# 6_channel_esp32_energy_meter_add-on_1_3_.net
KiCad netlist of a schematic drawn in EAGLE
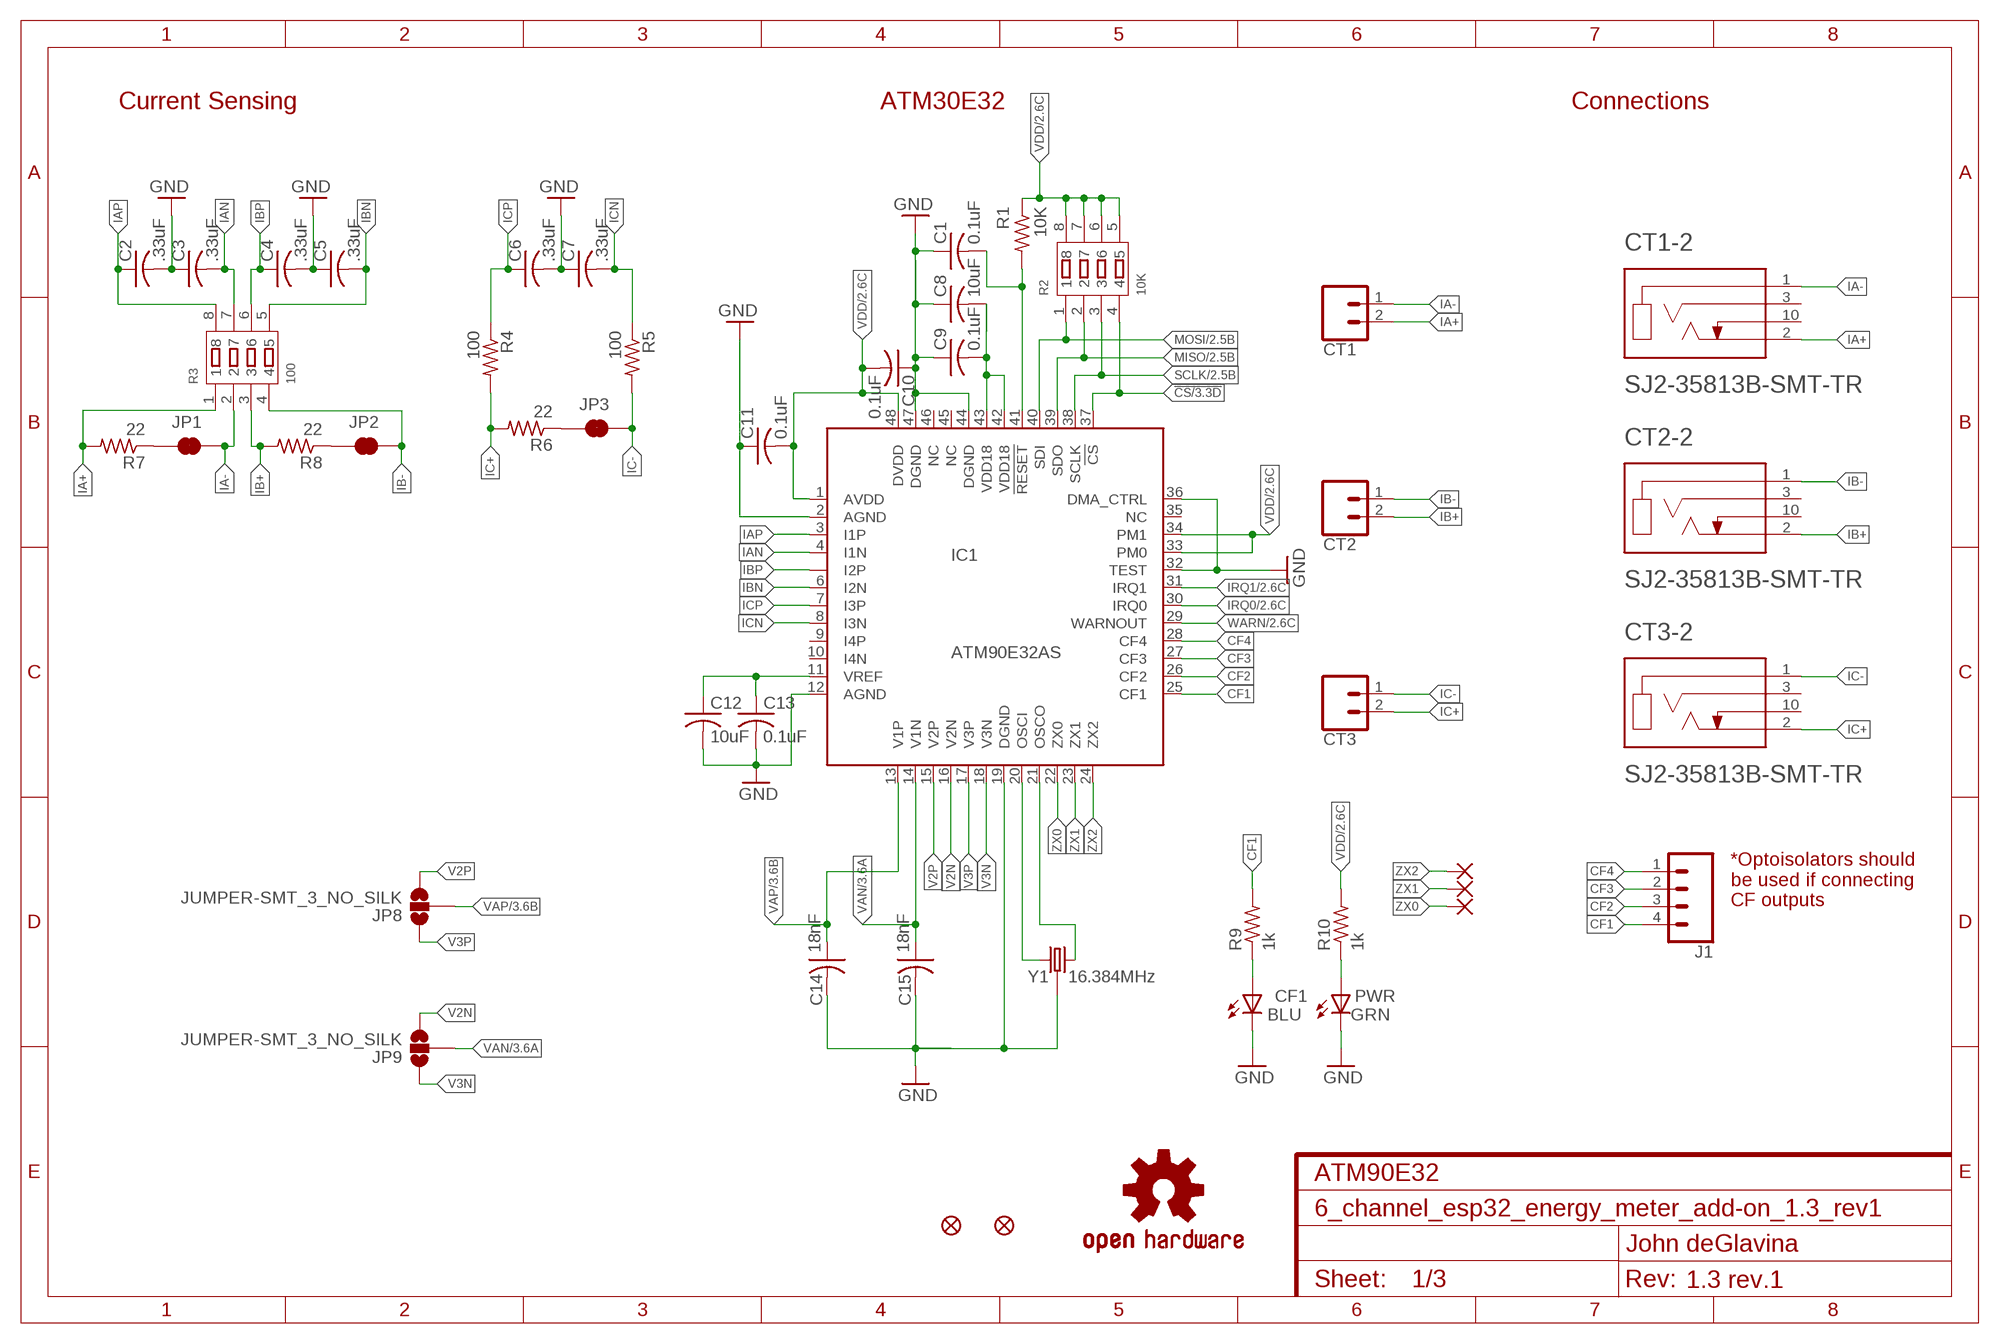
[diagram p0: schematic, sheet 1]
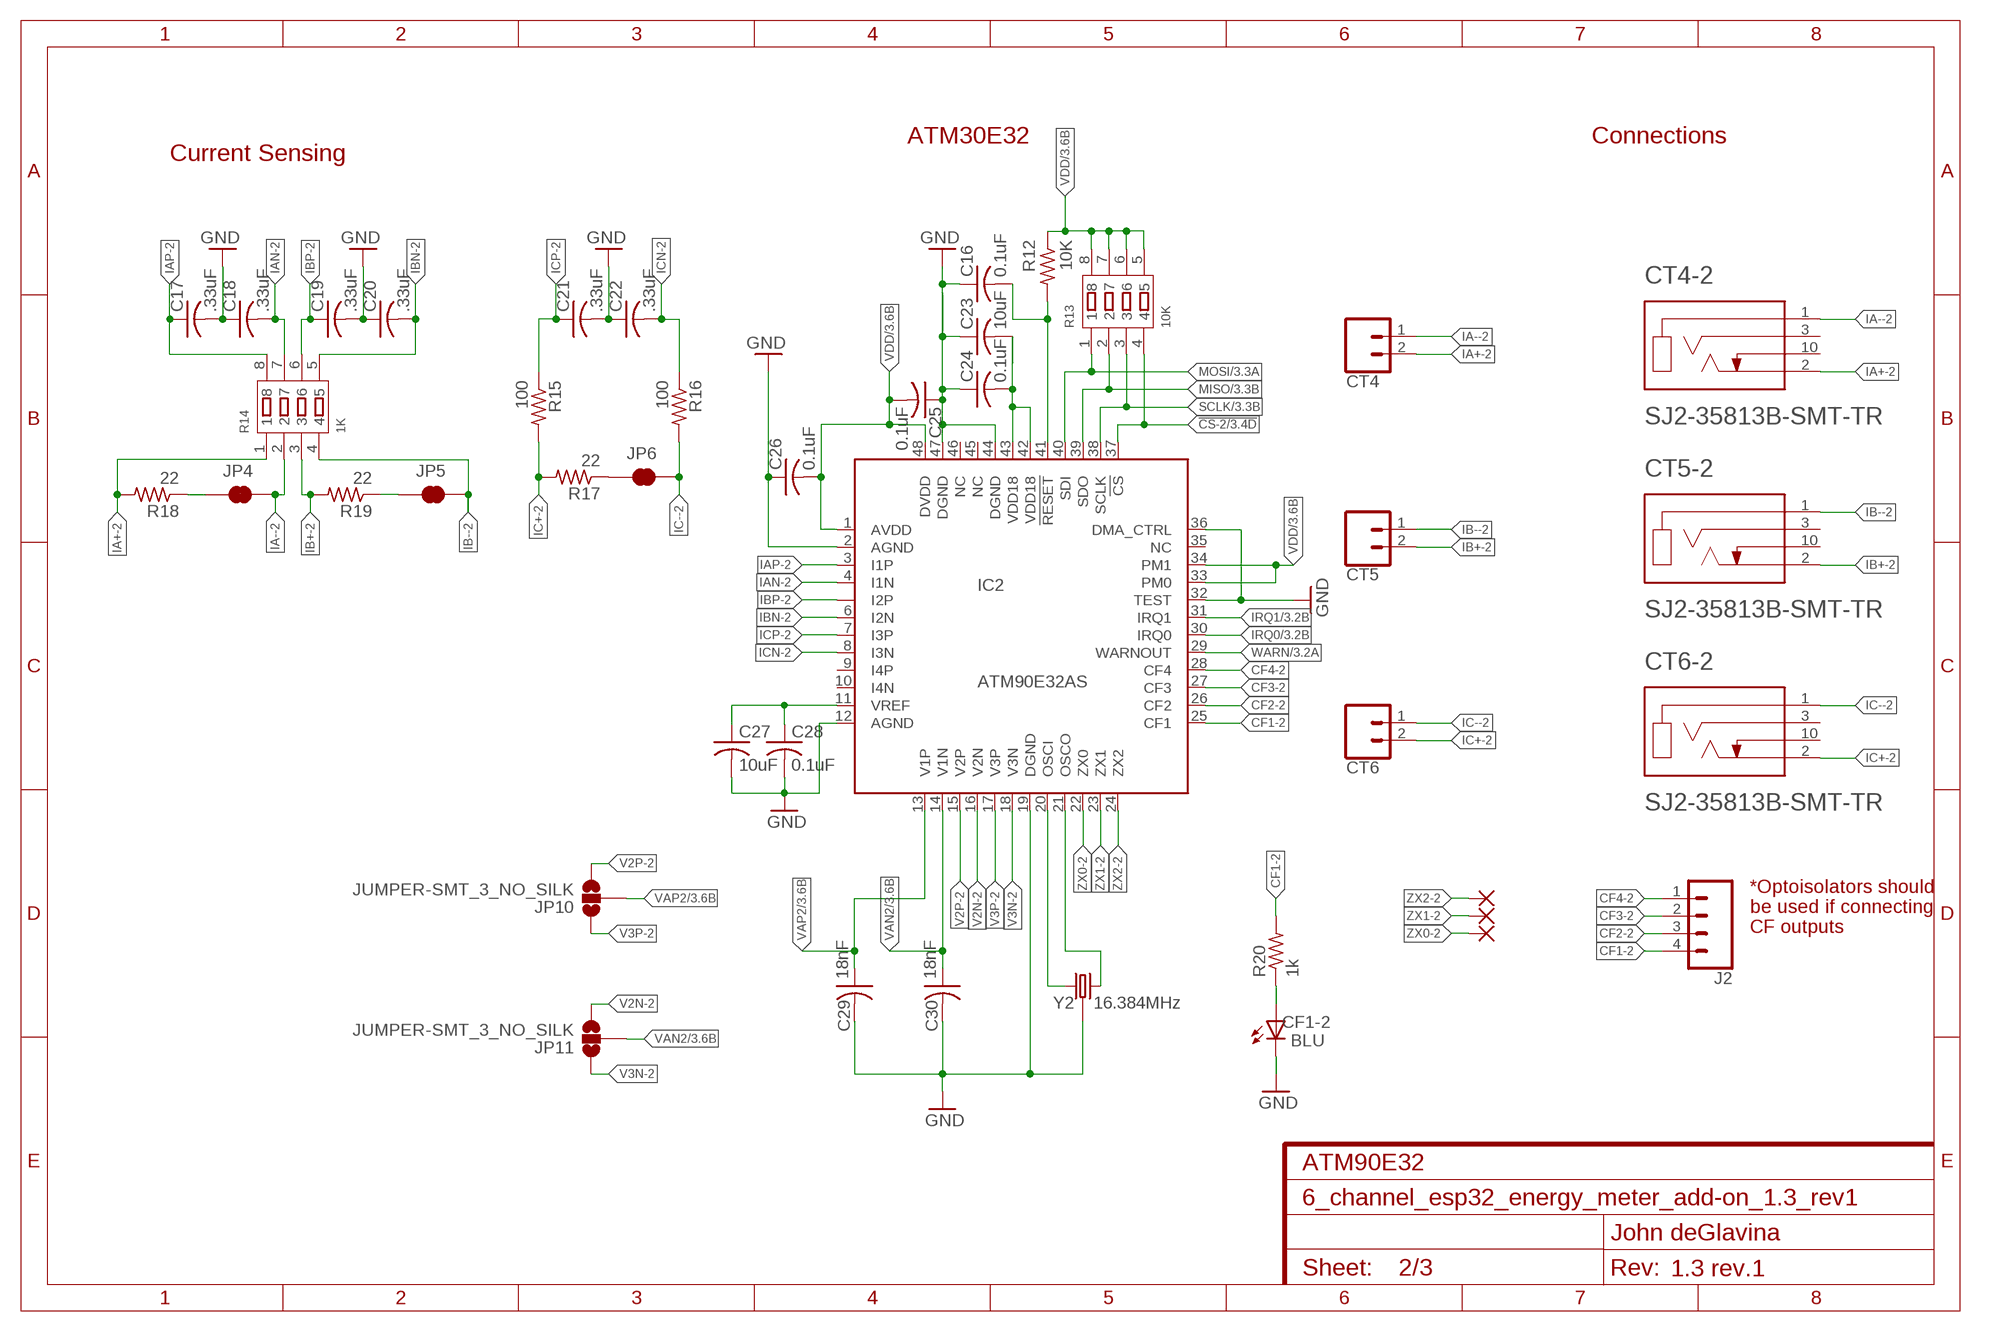
[diagram p1: schematic, sheet 2]
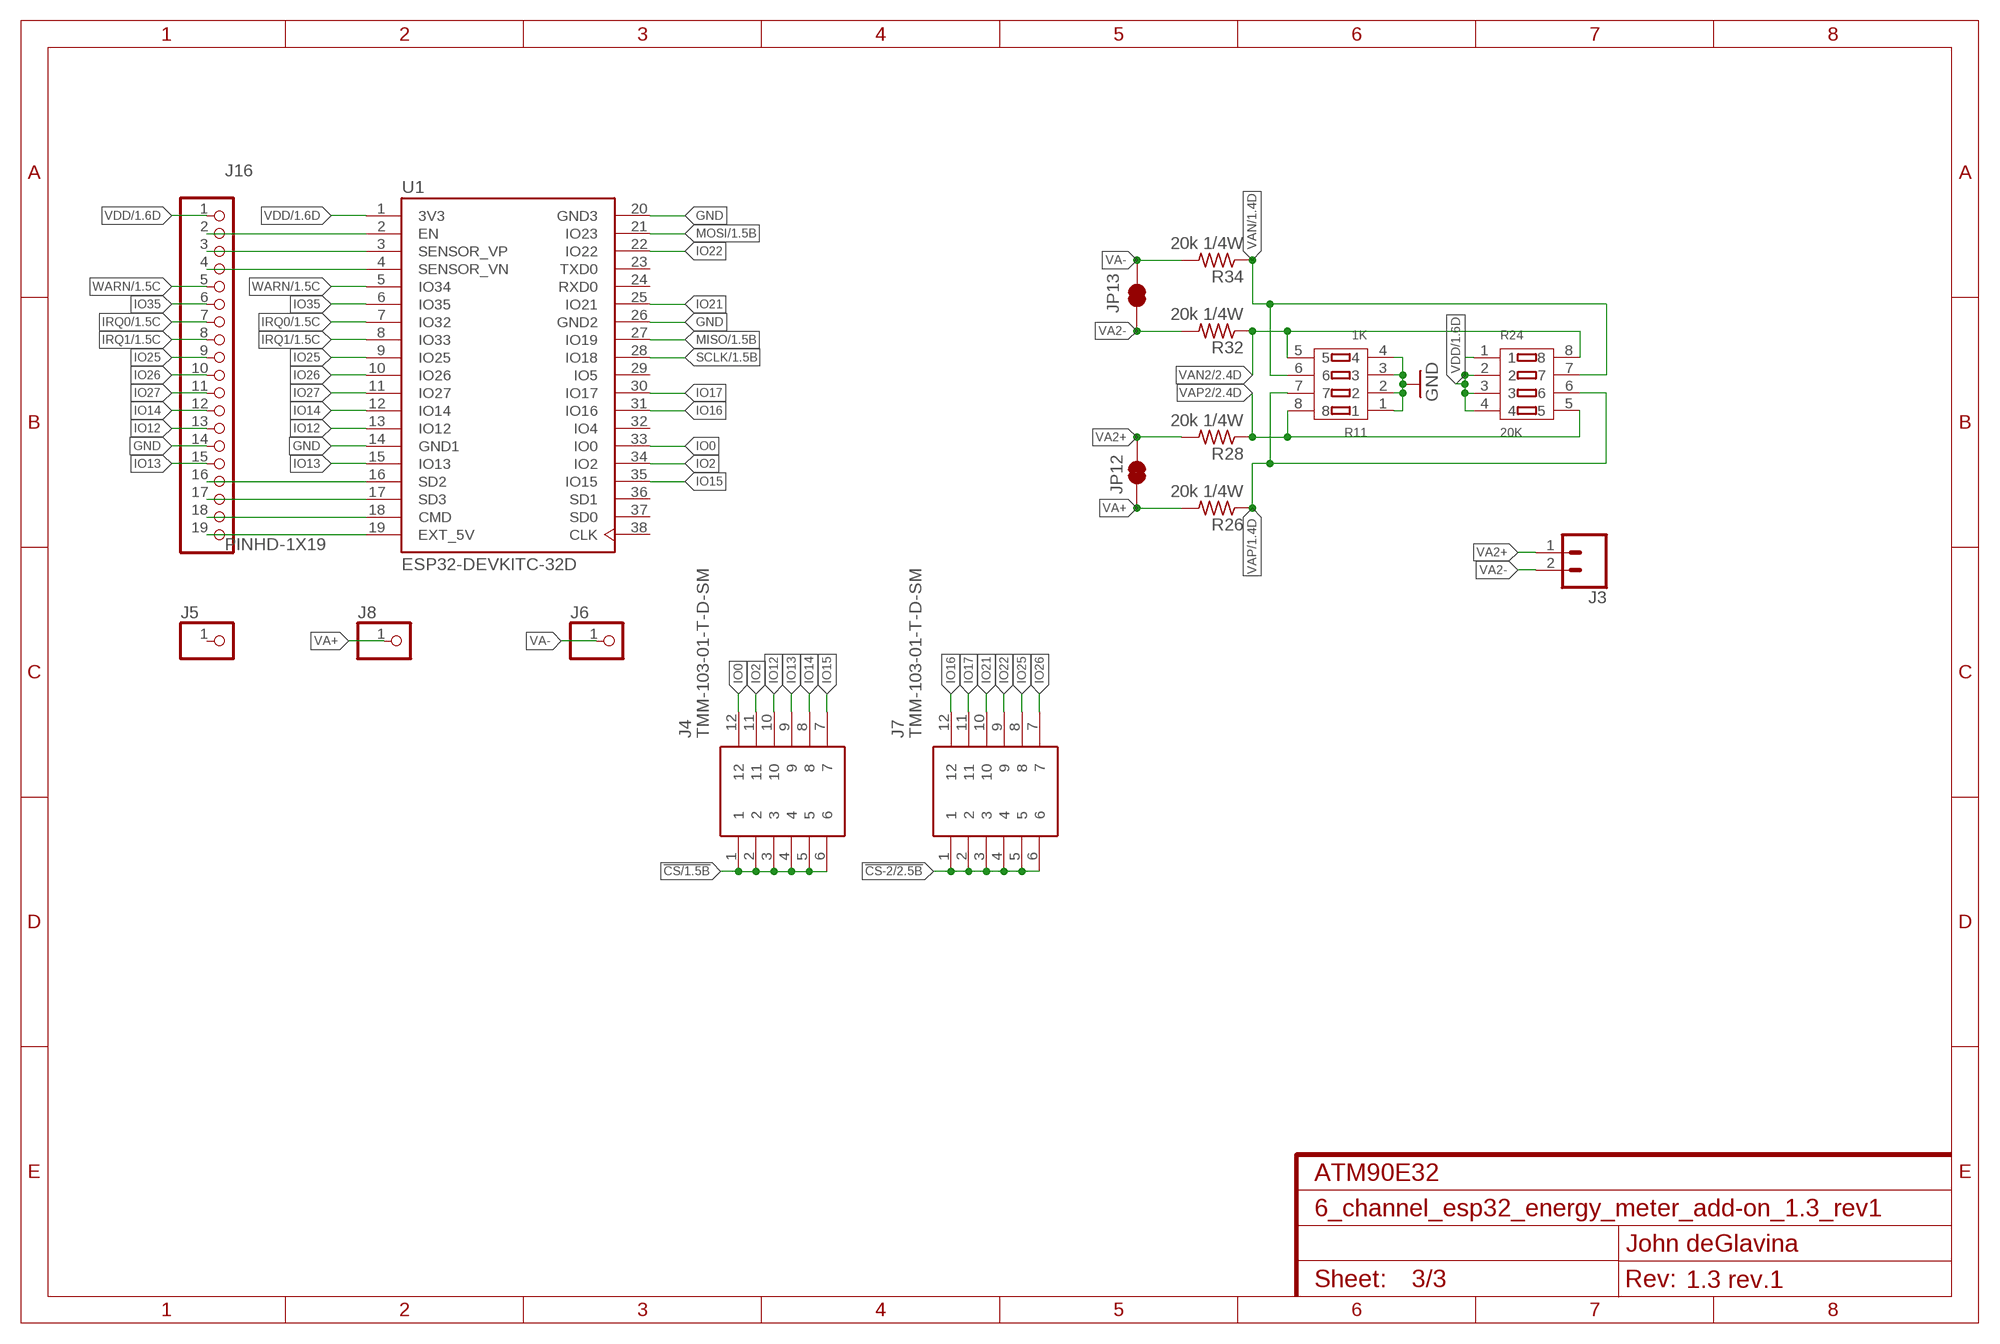
[diagram p2: schematic, sheet 3]

(export (version "E")
  (design (tool "Eeschema 10.0.6"))
  (components
    (comp (ref "C1")
      (value "0.1uF")
      (footprint "eagle-import:C0603")
      (libsource (lib "eagle-import") (part "C-USC0603"))
    )
    (comp (ref "C2")
      (value ".33uF")
      (footprint "eagle-import:C0603")
      (libsource (lib "eagle-import") (part "C-USC0603"))
    )
    (comp (ref "C3")
      (value ".33uF")
      (footprint "eagle-import:C0603")
      (libsource (lib "eagle-import") (part "C-USC0603"))
    )
    (comp (ref "C4")
      (value ".33uF")
      (footprint "eagle-import:C0603")
      (libsource (lib "eagle-import") (part "C-USC0603"))
    )
    (comp (ref "C5")
      (value ".33uF")
      (footprint "eagle-import:C0603")
      (libsource (lib "eagle-import") (part "C-USC0603"))
    )
    (comp (ref "C6")
      (value ".33uF")
      (footprint "eagle-import:C0603")
      (libsource (lib "eagle-import") (part "C-USC0603"))
    )
    (comp (ref "C7")
      (value ".33uF")
      (footprint "eagle-import:C0603")
      (libsource (lib "eagle-import") (part "C-USC0603"))
    )
    (comp (ref "C8")
      (value "10uF")
      (footprint "eagle-import:C0603")
      (libsource (lib "eagle-import") (part "C-USC0603"))
    )
    (comp (ref "C9")
      (value "0.1uF")
      (footprint "eagle-import:C0603")
      (libsource (lib "eagle-import") (part "C-USC0603"))
    )
    (comp (ref "C10")
      (value "0.1uF")
      (footprint "eagle-import:C0603")
      (libsource (lib "eagle-import") (part "C-USC0603"))
    )
    (comp (ref "C11")
      (value "0.1uF")
      (footprint "eagle-import:C0603")
      (libsource (lib "eagle-import") (part "C-USC0603"))
    )
    (comp (ref "C12")
      (value "10uF")
      (footprint "eagle-import:C0603")
      (libsource (lib "eagle-import") (part "C-USC0603"))
    )
    (comp (ref "C13")
      (value "0.1uF")
      (footprint "eagle-import:C0603")
      (libsource (lib "eagle-import") (part "C-USC0603"))
    )
    (comp (ref "C14")
      (value "18nF")
      (footprint "eagle-import:C0603")
      (libsource (lib "eagle-import") (part "C-USC0603"))
    )
    (comp (ref "C15")
      (value "18nF")
      (footprint "eagle-import:C0603")
      (libsource (lib "eagle-import") (part "C-USC0603"))
    )
    (comp (ref "CF1")
      (value "BLU")
      (footprint "eagle-import:CHIPLED_0603")
      (libsource (lib "eagle-import") (part "LEDCHIPLED_0603"))
    )
    (comp (ref "CT1")
      (value "CONN_023.5MM")
      (footprint "eagle-import:SCREWTERMINAL-3.5MM-2")
      (libsource (lib "eagle-import") (part "SparkFun-Connectors_8231346_CONN_023.5MM"))
    )
    (comp (ref "CT1-2")
      (value "SJ2-35813B-SMT-TR")
      (footprint "eagle-import:CUI_SJ2-35813B-SMT-TR")
      (fields (field (name "MANUFACTURER") "CUI"))
      (libsource (lib "eagle-import") (part "SJ2-35813B-SMT-TR"))
    )
    (comp (ref "CT2")
      (value "CONN_023.5MM")
      (footprint "eagle-import:SCREWTERMINAL-3.5MM-2")
      (libsource (lib "eagle-import") (part "SparkFun-Connectors_8231346_CONN_023.5MM"))
    )
    (comp (ref "CT2-2")
      (value "SJ2-35813B-SMT-TR")
      (footprint "eagle-import:CUI_SJ2-35813B-SMT-TR")
      (fields (field (name "MANUFACTURER") "CUI"))
      (libsource (lib "eagle-import") (part "SJ2-35813B-SMT-TR"))
    )
    (comp (ref "CT3")
      (value "CONN_023.5MM")
      (footprint "eagle-import:SCREWTERMINAL-3.5MM-2")
      (libsource (lib "eagle-import") (part "SparkFun-Connectors_8231346_CONN_023.5MM"))
    )
    (comp (ref "CT3-2")
      (value "SJ2-35813B-SMT-TR")
      (footprint "eagle-import:CUI_SJ2-35813B-SMT-TR")
      (fields (field (name "MANUFACTURER") "CUI"))
      (libsource (lib "eagle-import") (part "SJ2-35813B-SMT-TR"))
    )
    (comp (ref "FD1")
      (value "FIDUCIALUFIDUCIAL")
      (footprint "eagle-import:FIDUCIAL-MICRO")
      (libsource (lib "eagle-import") (part "FIDUCIALUFIDUCIAL"))
    )
    (comp (ref "FD2")
      (value "FIDUCIALUFIDUCIAL")
      (footprint "eagle-import:FIDUCIAL-MICRO")
      (libsource (lib "eagle-import") (part "FIDUCIALUFIDUCIAL"))
    )
    (comp (ref "IC1")
      (value "ATM90E32AS")
      (footprint "eagle-import:QFP50P900X900X120-48")
      (fields (field (name "SPICEPREFIX") "X"))
      (libsource (lib "eagle-import") (part "ATM90E36"))
    )
    (comp (ref "J1")
      (value "CONN_04")
      (footprint "eagle-import:1X04")
      (libsource (lib "eagle-import") (part "CONN_04"))
    )
    (comp (ref "JP1")
      (value "JUMPER-SMT_2_NC_TRACE_SILK")
      (footprint "eagle-import:SMT-JUMPER_2_NC_TRACE_SILK")
      (libsource (lib "eagle-import") (part "JUMPER-SMT_2_NC_TRACE_SILK"))
    )
    (comp (ref "JP2")
      (value "JUMPER-SMT_2_NC_TRACE_SILK")
      (footprint "eagle-import:SMT-JUMPER_2_NC_TRACE_SILK")
      (libsource (lib "eagle-import") (part "JUMPER-SMT_2_NC_TRACE_SILK"))
    )
    (comp (ref "JP3")
      (value "JUMPER-SMT_2_NC_TRACE_SILK")
      (footprint "eagle-import:SMT-JUMPER_2_NC_TRACE_SILK")
      (libsource (lib "eagle-import") (part "JUMPER-SMT_2_NC_TRACE_SILK"))
    )
    (comp (ref "JP8")
      (value "JUMPER-SMT_3_NO_SILK")
      (footprint "eagle-import:SMT-JUMPER_3_NO_SILK")
      (libsource (lib "eagle-import") (part "JUMPER-SMT_3_NO_SILK"))
    )
    (comp (ref "JP9")
      (value "JUMPER-SMT_3_NO_SILK")
      (footprint "eagle-import:SMT-JUMPER_3_NO_SILK")
      (libsource (lib "eagle-import") (part "JUMPER-SMT_3_NO_SILK"))
    )
    (comp (ref "LOGO1")
      (value "OSHW-LOGOS")
      (footprint "eagle-import:OSHW-LOGO-S")
      (libsource (lib "eagle-import") (part "OSHW-LOGOS"))
    )
    (comp (ref "PWR")
      (value "GRN")
      (footprint "eagle-import:CHIPLED_0603")
      (libsource (lib "eagle-import") (part "LEDCHIPLED_0603"))
    )
    (comp (ref "R1")
      (value "10K")
      (footprint "eagle-import:R0603")
      (libsource (lib "eagle-import") (part "R-US_R0603"))
    )
    (comp (ref "R2")
      (value "10K")
      (footprint "eagle-import:RA1206-8")
      (fields (field (name "MPN") "Chip-Array-Series-1%"))
      (libsource (lib "eagle-import") (part "SMD-RES-ARRAY-1K-4R(RA1206-8)"))
    )
    (comp (ref "R3")
      (value "100")
      (footprint "eagle-import:RA1206-8")
      (fields (field (name "MPN") "Chip-Array-Series-1%"))
      (libsource (lib "eagle-import") (part "SMD-RES-ARRAY-1K-4R(RA1206-8)"))
    )
    (comp (ref "R4")
      (value "100")
      (footprint "eagle-import:R0603")
      (libsource (lib "eagle-import") (part "R-US_R0603"))
    )
    (comp (ref "R5")
      (value "100")
      (footprint "eagle-import:R0603")
      (libsource (lib "eagle-import") (part "R-US_R0603"))
    )
    (comp (ref "R6")
      (value "22")
      (footprint "eagle-import:R0603")
      (libsource (lib "eagle-import") (part "R-US_R0603"))
    )
    (comp (ref "R7")
      (value "22")
      (footprint "eagle-import:R0603")
      (libsource (lib "eagle-import") (part "R-US_R0603"))
    )
    (comp (ref "R8")
      (value "22")
      (footprint "eagle-import:R0603")
      (libsource (lib "eagle-import") (part "R-US_R0603"))
    )
    (comp (ref "R9")
      (value "1k")
      (footprint "eagle-import:R0603")
      (libsource (lib "eagle-import") (part "R-US_R0603"))
    )
    (comp (ref "R10")
      (value "1k")
      (footprint "eagle-import:R0603")
      (libsource (lib "eagle-import") (part "R-US_R0603"))
    )
    (comp (ref "Y1")
      (value "16.384MHz")
      (footprint "eagle-import:CRYSTAL-SMD-3.2X2.5MM")
      (libsource (lib "eagle-import") (part "CRYSTAL-GROUNDEDSMD-3.2X2.5"))
    )
    (comp (ref "ZX0")
      (value "WIREPADSMD1,27-254")
      (footprint "eagle-import:SMD1,27-2,54")
      (libsource (lib "eagle-import") (part "WIREPADSMD1,27-254"))
    )
    (comp (ref "ZX1")
      (value "WIREPADSMD1,27-254")
      (footprint "eagle-import:SMD1,27-2,54")
      (libsource (lib "eagle-import") (part "WIREPADSMD1,27-254"))
    )
    (comp (ref "ZX2")
      (value "WIREPADSMD1,27-254")
      (footprint "eagle-import:SMD1,27-2,54")
      (libsource (lib "eagle-import") (part "WIREPADSMD1,27-254"))
    )
    (comp (ref "J3")
      (value "CONN_02")
      (footprint "eagle-import:1X02")
      (libsource (lib "eagle-import") (part "CONN_02"))
    )
    (comp (ref "J4")
      (value "TMM-103-01-T-D-SM")
      (footprint "eagle-import:SOP200P706X597-12N")
      (libsource (lib "eagle-import") (part "TMM-103-01-T-D-SM"))
    )
    (comp (ref "J5")
      (value "PINHD1X1-SM1X01_SM")
      (footprint "eagle-import:1X01-SM")
      (libsource (lib "eagle-import") (part "PINHD1X1-SM1X01_SM"))
    )
    (comp (ref "J6")
      (value "PINHD1X1-SM1X01_SM")
      (footprint "eagle-import:1X01-SM")
      (libsource (lib "eagle-import") (part "PINHD1X1-SM1X01_SM"))
    )
    (comp (ref "J7")
      (value "TMM-103-01-T-D-SM")
      (footprint "eagle-import:SOP200P706X597-12N")
      (libsource (lib "eagle-import") (part "TMM-103-01-T-D-SM"))
    )
    (comp (ref "J8")
      (value "PINHD1X1-SM1X01_SM")
      (footprint "eagle-import:1X01-SM")
      (libsource (lib "eagle-import") (part "PINHD1X1-SM1X01_SM"))
    )
    (comp (ref "J16")
      (value "PINHD-1X19")
      (footprint "eagle-import:1X19")
      (fields (field (name "SPICEPREFIX") "X"))
      (libsource (lib "eagle-import") (part "PINHD-1X19"))
    )
    (comp (ref "JP12")
      (value "JUMPER-SMT_2_NC_TRACE_SILK")
      (footprint "eagle-import:SMT-JUMPER_2_NC_TRACE_SILK")
      (libsource (lib "eagle-import") (part "JUMPER-SMT_2_NC_TRACE_SILK"))
    )
    (comp (ref "JP13")
      (value "JUMPER-SMT_2_NC_TRACE_SILK")
      (footprint "eagle-import:SMT-JUMPER_2_NC_TRACE_SILK")
      (libsource (lib "eagle-import") (part "JUMPER-SMT_2_NC_TRACE_SILK"))
    )
    (comp (ref "R11")
      (value "1K")
      (footprint "eagle-import:RA1206-8")
      (fields (field (name "MPN") "Chip-Array-Series-1%"))
      (libsource (lib "eagle-import") (part "SMD-RES-ARRAY-1K-4R(RA1206-8)"))
    )
    (comp (ref "R24")
      (value "20K")
      (footprint "eagle-import:RA1206-8")
      (fields (field (name "MPN") "Chip-Array-Series-1%"))
      (libsource (lib "eagle-import") (part "SMD-RES-ARRAY-1K-4R(RA1206-8)"))
    )
    (comp (ref "R26")
      (value "20k 1/4W")
      (footprint "eagle-import:R0603")
      (libsource (lib "eagle-import") (part "R-US_R0603"))
    )
    (comp (ref "R28")
      (value "20k 1/4W")
      (footprint "eagle-import:R0603")
      (libsource (lib "eagle-import") (part "R-US_R0603"))
    )
    (comp (ref "R32")
      (value "20k 1/4W")
      (footprint "eagle-import:R0603")
      (libsource (lib "eagle-import") (part "R-US_R0603"))
    )
    (comp (ref "R34")
      (value "20k 1/4W")
      (footprint "eagle-import:R0603")
      (libsource (lib "eagle-import") (part "R-US_R0603"))
    )
    (comp (ref "U1")
      (value "ESP32-DEVKITC-32D")
      (footprint "eagle-import:MODULE_ESP32-DEVKITC-32D")
      (fields (field (name "MF") "Espressif Systems"))
      (libsource (lib "eagle-import") (part "ESP32-DEVKITC-32D"))
    )
    (comp (ref "C16")
      (value "0.1uF")
      (footprint "eagle-import:C0603")
      (libsource (lib "eagle-import") (part "C-USC0603"))
    )
    (comp (ref "C17")
      (value ".33uF")
      (footprint "eagle-import:C0603")
      (libsource (lib "eagle-import") (part "C-USC0603"))
    )
    (comp (ref "C18")
      (value ".33uF")
      (footprint "eagle-import:C0603")
      (libsource (lib "eagle-import") (part "C-USC0603"))
    )
    (comp (ref "C19")
      (value ".33uF")
      (footprint "eagle-import:C0603")
      (libsource (lib "eagle-import") (part "C-USC0603"))
    )
    (comp (ref "C20")
      (value ".33uF")
      (footprint "eagle-import:C0603")
      (libsource (lib "eagle-import") (part "C-USC0603"))
    )
    (comp (ref "C21")
      (value ".33uF")
      (footprint "eagle-import:C0603")
      (libsource (lib "eagle-import") (part "C-USC0603"))
    )
    (comp (ref "C22")
      (value ".33uF")
      (footprint "eagle-import:C0603")
      (libsource (lib "eagle-import") (part "C-USC0603"))
    )
    (comp (ref "C23")
      (value "10uF")
      (footprint "eagle-import:C0603")
      (libsource (lib "eagle-import") (part "C-USC0603"))
    )
    (comp (ref "C24")
      (value "0.1uF")
      (footprint "eagle-import:C0603")
      (libsource (lib "eagle-import") (part "C-USC0603"))
    )
    (comp (ref "C25")
      (value "0.1uF")
      (footprint "eagle-import:C0603")
      (libsource (lib "eagle-import") (part "C-USC0603"))
    )
    (comp (ref "C26")
      (value "0.1uF")
      (footprint "eagle-import:C0603")
      (libsource (lib "eagle-import") (part "C-USC0603"))
    )
    (comp (ref "C27")
      (value "10uF")
      (footprint "eagle-import:C0603")
      (libsource (lib "eagle-import") (part "C-USC0603"))
    )
    (comp (ref "C28")
      (value "0.1uF")
      (footprint "eagle-import:C0603")
      (libsource (lib "eagle-import") (part "C-USC0603"))
    )
    (comp (ref "C29")
      (value "18nF")
      (footprint "eagle-import:C0603")
      (libsource (lib "eagle-import") (part "C-USC0603"))
    )
    (comp (ref "C30")
      (value "18nF")
      (footprint "eagle-import:C0603")
      (libsource (lib "eagle-import") (part "C-USC0603"))
    )
    (comp (ref "CF1-2")
      (value "BLU")
      (footprint "eagle-import:CHIPLED_0603")
      (libsource (lib "eagle-import") (part "LEDCHIPLED_0603"))
    )
    (comp (ref "CT4")
      (value "CONN_023.5MM")
      (footprint "eagle-import:SCREWTERMINAL-3.5MM-2")
      (libsource (lib "eagle-import") (part "SparkFun-Connectors_8231346_CONN_023.5MM"))
    )
    (comp (ref "CT4-2")
      (value "SJ2-35813B-SMT-TR")
      (footprint "eagle-import:CUI_SJ2-35813B-SMT-TR")
      (fields (field (name "MANUFACTURER") "CUI"))
      (libsource (lib "eagle-import") (part "SJ2-35813B-SMT-TR"))
    )
    (comp (ref "CT5")
      (value "CONN_023.5MM")
      (footprint "eagle-import:SCREWTERMINAL-3.5MM-2")
      (libsource (lib "eagle-import") (part "SparkFun-Connectors_8231346_CONN_023.5MM"))
    )
    (comp (ref "CT5-2")
      (value "SJ2-35813B-SMT-TR")
      (footprint "eagle-import:CUI_SJ2-35813B-SMT-TR")
      (fields (field (name "MANUFACTURER") "CUI"))
      (libsource (lib "eagle-import") (part "SJ2-35813B-SMT-TR"))
    )
    (comp (ref "CT6")
      (value "CONN_023.5MM")
      (footprint "eagle-import:SCREWTERMINAL-3.5MM-2")
      (libsource (lib "eagle-import") (part "SparkFun-Connectors_8231346_CONN_023.5MM"))
    )
    (comp (ref "CT6-2")
      (value "SJ2-35813B-SMT-TR")
      (footprint "eagle-import:CUI_SJ2-35813B-SMT-TR")
      (fields (field (name "MANUFACTURER") "CUI"))
      (libsource (lib "eagle-import") (part "SJ2-35813B-SMT-TR"))
    )
    (comp (ref "IC2")
      (value "ATM90E32AS")
      (footprint "eagle-import:QFP50P900X900X120-48")
      (fields (field (name "SPICEPREFIX") "X"))
      (libsource (lib "eagle-import") (part "ATM90E36"))
    )
    (comp (ref "J2")
      (value "CONN_04")
      (footprint "eagle-import:1X04")
      (libsource (lib "eagle-import") (part "CONN_04"))
    )
    (comp (ref "JP4")
      (value "JUMPER-SMT_2_NC_TRACE_SILK")
      (footprint "eagle-import:SMT-JUMPER_2_NC_TRACE_SILK")
      (libsource (lib "eagle-import") (part "JUMPER-SMT_2_NC_TRACE_SILK"))
    )
    (comp (ref "JP5")
      (value "JUMPER-SMT_2_NC_TRACE_SILK")
      (footprint "eagle-import:SMT-JUMPER_2_NC_TRACE_SILK")
      (libsource (lib "eagle-import") (part "JUMPER-SMT_2_NC_TRACE_SILK"))
    )
    (comp (ref "JP6")
      (value "JUMPER-SMT_2_NC_TRACE_SILK")
      (footprint "eagle-import:SMT-JUMPER_2_NC_TRACE_SILK")
      (libsource (lib "eagle-import") (part "JUMPER-SMT_2_NC_TRACE_SILK"))
    )
    (comp (ref "JP10")
      (value "JUMPER-SMT_3_NO_SILK")
      (footprint "eagle-import:SMT-JUMPER_3_NO_SILK")
      (libsource (lib "eagle-import") (part "JUMPER-SMT_3_NO_SILK"))
    )
    (comp (ref "JP11")
      (value "JUMPER-SMT_3_NO_SILK")
      (footprint "eagle-import:SMT-JUMPER_3_NO_SILK")
      (libsource (lib "eagle-import") (part "JUMPER-SMT_3_NO_SILK"))
    )
    (comp (ref "R12")
      (value "10K")
      (footprint "eagle-import:R0603")
      (libsource (lib "eagle-import") (part "R-US_R0603"))
    )
    (comp (ref "R13")
      (value "10K")
      (footprint "eagle-import:RA1206-8")
      (fields (field (name "MPN") "Chip-Array-Series-1%"))
      (libsource (lib "eagle-import") (part "SMD-RES-ARRAY-1K-4R(RA1206-8)"))
    )
    (comp (ref "R14")
      (value "1K")
      (footprint "eagle-import:RA1206-8")
      (fields (field (name "MPN") "Chip-Array-Series-1%"))
      (libsource (lib "eagle-import") (part "SMD-RES-ARRAY-1K-4R(RA1206-8)"))
    )
    (comp (ref "R15")
      (value "100")
      (footprint "eagle-import:R0603")
      (libsource (lib "eagle-import") (part "R-US_R0603"))
    )
    (comp (ref "R16")
      (value "100")
      (footprint "eagle-import:R0603")
      (libsource (lib "eagle-import") (part "R-US_R0603"))
    )
    (comp (ref "R17")
      (value "22")
      (footprint "eagle-import:R0603")
      (libsource (lib "eagle-import") (part "R-US_R0603"))
    )
    (comp (ref "R18")
      (value "22")
      (footprint "eagle-import:R0603")
      (libsource (lib "eagle-import") (part "R-US_R0603"))
    )
    (comp (ref "R19")
      (value "22")
      (footprint "eagle-import:R0603")
      (libsource (lib "eagle-import") (part "R-US_R0603"))
    )
    (comp (ref "R20")
      (value "1k")
      (footprint "eagle-import:R0603")
      (libsource (lib "eagle-import") (part "R-US_R0603"))
    )
    (comp (ref "Y2")
      (value "16.384MHz")
      (footprint "eagle-import:CRYSTAL-SMD-3.2X2.5MM")
      (libsource (lib "eagle-import") (part "CRYSTAL-GROUNDEDSMD-3.2X2.5"))
    )
    (comp (ref "ZX0-2")
      (value "WIREPADSMD1,27-254")
      (footprint "eagle-import:SMD1,27-2,54")
      (libsource (lib "eagle-import") (part "WIREPADSMD1,27-254"))
    )
    (comp (ref "ZX1-2")
      (value "WIREPADSMD1,27-254")
      (footprint "eagle-import:SMD1,27-2,54")
      (libsource (lib "eagle-import") (part "WIREPADSMD1,27-254"))
    )
    (comp (ref "ZX2-2")
      (value "WIREPADSMD1,27-254")
      (footprint "eagle-import:SMD1,27-2,54")
      (libsource (lib "eagle-import") (part "WIREPADSMD1,27-254"))
    )
  )
  (nets
    (net (code "1") (name "CF1") (class "Default")
      (node (ref "IC1") (pin "25") (pinfunction "CF1_25") (pintype "output"))
      (node (ref "J1") (pin "4") (pinfunction "4_4") (pintype "passive"))
      (node (ref "R9") (pin "2") (pinfunction "2_2") (pintype "passive"))
    )
    (net (code "2") (name "CF1-2") (class "Default")
      (node (ref "IC2") (pin "25") (pinfunction "CF1_25") (pintype "output"))
      (node (ref "J2") (pin "4") (pinfunction "4_4") (pintype "passive"))
      (node (ref "R20") (pin "2") (pinfunction "2_2") (pintype "passive"))
    )
    (net (code "3") (name "CF2") (class "Default")
      (node (ref "IC1") (pin "26") (pinfunction "CF2_26") (pintype "output"))
      (node (ref "J1") (pin "3") (pinfunction "3_3") (pintype "passive"))
    )
    (net (code "4") (name "CF2-2") (class "Default")
      (node (ref "IC2") (pin "26") (pinfunction "CF2_26") (pintype "output"))
      (node (ref "J2") (pin "3") (pinfunction "3_3") (pintype "passive"))
    )
    (net (code "5") (name "CF3") (class "Default")
      (node (ref "IC1") (pin "27") (pinfunction "CF3_27") (pintype "output"))
      (node (ref "J1") (pin "2") (pinfunction "2_2") (pintype "passive"))
    )
    (net (code "6") (name "CF3-2") (class "Default")
      (node (ref "IC2") (pin "27") (pinfunction "CF3_27") (pintype "output"))
      (node (ref "J2") (pin "2") (pinfunction "2_2") (pintype "passive"))
    )
    (net (code "7") (name "CF4") (class "Default")
      (node (ref "IC1") (pin "28") (pinfunction "CF4_28") (pintype "output"))
      (node (ref "J1") (pin "1") (pinfunction "1_1") (pintype "passive"))
    )
    (net (code "8") (name "CF4-2") (class "Default")
      (node (ref "IC2") (pin "28") (pinfunction "CF4_28") (pintype "output"))
      (node (ref "J2") (pin "1") (pinfunction "1_1") (pintype "passive"))
    )
    (net (code "9") (name "GND") (class "Default")
      (node (ref "C1") (pin "1") (pinfunction "1_1") (pintype "passive"))
      (node (ref "C10") (pin "1") (pinfunction "1_1") (pintype "passive"))
      (node (ref "C11") (pin "1") (pinfunction "1_1") (pintype "passive"))
      (node (ref "C12") (pin "2") (pinfunction "2_2") (pintype "passive"))
      (node (ref "C13") (pin "2") (pinfunction "2_2") (pintype "passive"))
      (node (ref "C14") (pin "2") (pinfunction "2_2") (pintype "passive"))
      (node (ref "C15") (pin "2") (pinfunction "2_2") (pintype "passive"))
      (node (ref "C16") (pin "1") (pinfunction "1_1") (pintype "passive"))
      (node (ref "C17") (pin "2") (pinfunction "2_2") (pintype "passive"))
      (node (ref "C18") (pin "1") (pinfunction "1_1") (pintype "passive"))
      (node (ref "C19") (pin "2") (pinfunction "2_2") (pintype "passive"))
      (node (ref "C2") (pin "2") (pinfunction "2_2") (pintype "passive"))
      (node (ref "C20") (pin "1") (pinfunction "1_1") (pintype "passive"))
      (node (ref "C21") (pin "2") (pinfunction "2_2") (pintype "passive"))
      (node (ref "C22") (pin "1") (pinfunction "1_1") (pintype "passive"))
      (node (ref "C23") (pin "1") (pinfunction "1_1") (pintype "passive"))
      (node (ref "C24") (pin "1") (pinfunction "1_1") (pintype "passive"))
      (node (ref "C25") (pin "1") (pinfunction "1_1") (pintype "passive"))
      (node (ref "C26") (pin "1") (pinfunction "1_1") (pintype "passive"))
      (node (ref "C27") (pin "2") (pinfunction "2_2") (pintype "passive"))
      (node (ref "C28") (pin "2") (pinfunction "2_2") (pintype "passive"))
      (node (ref "C29") (pin "2") (pinfunction "2_2") (pintype "passive"))
      (node (ref "C3") (pin "1") (pinfunction "1_1") (pintype "passive"))
      (node (ref "C30") (pin "2") (pinfunction "2_2") (pintype "passive"))
      (node (ref "C4") (pin "2") (pinfunction "2_2") (pintype "passive"))
      (node (ref "C5") (pin "1") (pinfunction "1_1") (pintype "passive"))
      (node (ref "C6") (pin "2") (pinfunction "2_2") (pintype "passive"))
      (node (ref "C7") (pin "1") (pinfunction "1_1") (pintype "passive"))
      (node (ref "C8") (pin "1") (pinfunction "1_1") (pintype "passive"))
      (node (ref "C9") (pin "1") (pinfunction "1_1") (pintype "passive"))
      (node (ref "CF1") (pin "C") (pinfunction "C_C") (pintype "passive"))
      (node (ref "CF1-2") (pin "C") (pinfunction "C_C") (pintype "passive"))
      (node (ref "IC1") (pin "12") (pinfunction "AGND_12") (pintype "power_in"))
      (node (ref "IC1") (pin "19") (pinfunction "DGND_19") (pintype "power_in"))
      (node (ref "IC1") (pin "2") (pinfunction "AGND_2") (pintype "power_in"))
      (node (ref "IC1") (pin "32") (pinfunction "TEST_32") (pintype "power_in"))
      (node (ref "IC1") (pin "36") (pinfunction "DMA_CTRL_36") (pintype "input"))
      (node (ref "IC1") (pin "44") (pinfunction "DGND_44") (pintype "power_in"))
      (node (ref "IC1") (pin "47") (pinfunction "DGND_47") (pintype "power_in"))
      (node (ref "IC2") (pin "12") (pinfunction "AGND_12") (pintype "power_in"))
      (node (ref "IC2") (pin "19") (pinfunction "DGND_19") (pintype "power_in"))
      (node (ref "IC2") (pin "2") (pinfunction "AGND_2") (pintype "power_in"))
      (node (ref "IC2") (pin "32") (pinfunction "TEST_32") (pintype "power_in"))
      (node (ref "IC2") (pin "36") (pinfunction "DMA_CTRL_36") (pintype "input"))
      (node (ref "IC2") (pin "44") (pinfunction "DGND_44") (pintype "power_in"))
      (node (ref "IC2") (pin "47") (pinfunction "DGND_47") (pintype "power_in"))
      (node (ref "J16") (pin "14") (pinfunction "14_14") (pintype "passive"))
      (node (ref "PWR") (pin "C") (pinfunction "C_C") (pintype "passive"))
      (node (ref "R11") (pin "1") (pinfunction "1_1") (pintype "bidirectional"))
      (node (ref "R11") (pin "2") (pinfunction "2_2") (pintype "bidirectional"))
      (node (ref "R11") (pin "3") (pinfunction "3_3") (pintype "bidirectional"))
      (node (ref "R11") (pin "4") (pinfunction "4_4") (pintype "bidirectional"))
      (node (ref "U1") (pin "14") (pinfunction "GND1_14") (pintype "power_in"))
      (node (ref "U1") (pin "20") (pinfunction "GND3_20") (pintype "power_in"))
      (node (ref "U1") (pin "26") (pinfunction "GND2_26") (pintype "power_in"))
      (node (ref "Y1") (pin "2") (pinfunction "3_2") (pintype "passive"))
      (node (ref "Y1") (pin "4") (pinfunction "3_4") (pintype "passive"))
      (node (ref "Y2") (pin "2") (pinfunction "3_2") (pintype "passive"))
      (node (ref "Y2") (pin "4") (pinfunction "3_4") (pintype "passive"))
    )
    (net (code "10") (name "IA+") (class "Default")
      (node (ref "CT1") (pin "2") (pinfunction "2_2") (pintype "passive"))
      (node (ref "CT1-2") (pin "2") (pinfunction "TIP_2") (pintype "passive"))
      (node (ref "R3") (pin "1") (pinfunction "1_1") (pintype "bidirectional"))
      (node (ref "R7") (pin "2") (pinfunction "2_2") (pintype "passive"))
    )
    (net (code "11") (name "IA+-2") (class "Default")
      (node (ref "CT4") (pin "2") (pinfunction "2_2") (pintype "passive"))
      (node (ref "CT4-2") (pin "2") (pinfunction "TIP_2") (pintype "passive"))
      (node (ref "R14") (pin "1") (pinfunction "1_1") (pintype "bidirectional"))
      (node (ref "R18") (pin "2") (pinfunction "2_2") (pintype "passive"))
    )
    (net (code "12") (name "IA-") (class "Default")
      (node (ref "CT1") (pin "1") (pinfunction "1_1") (pintype "passive"))
      (node (ref "CT1-2") (pin "1") (pinfunction "SLEEVE_1") (pintype "passive"))
      (node (ref "JP1") (pin "2") (pinfunction "2_2") (pintype "passive"))
      (node (ref "R3") (pin "2") (pinfunction "2_2") (pintype "bidirectional"))
    )
    (net (code "13") (name "IA--2") (class "Default")
      (node (ref "CT4") (pin "1") (pinfunction "1_1") (pintype "passive"))
      (node (ref "CT4-2") (pin "1") (pinfunction "SLEEVE_1") (pintype "passive"))
      (node (ref "JP4") (pin "2") (pinfunction "2_2") (pintype "passive"))
      (node (ref "R14") (pin "2") (pinfunction "2_2") (pintype "bidirectional"))
    )
    (net (code "14") (name "IAN") (class "Default")
      (node (ref "C3") (pin "2") (pinfunction "2_2") (pintype "passive"))
      (node (ref "IC1") (pin "4") (pinfunction "I1N_4") (pintype "input"))
      (node (ref "R3") (pin "7") (pinfunction "7_7") (pintype "bidirectional"))
    )
    (net (code "15") (name "IAN-2") (class "Default")
      (node (ref "C18") (pin "2") (pinfunction "2_2") (pintype "passive"))
      (node (ref "IC2") (pin "4") (pinfunction "I1N_4") (pintype "input"))
      (node (ref "R14") (pin "7") (pinfunction "7_7") (pintype "bidirectional"))
    )
    (net (code "16") (name "IAP") (class "Default")
      (node (ref "C2") (pin "1") (pinfunction "1_1") (pintype "passive"))
      (node (ref "IC1") (pin "3") (pinfunction "I1P_3") (pintype "input"))
      (node (ref "R3") (pin "8") (pinfunction "8_8") (pintype "bidirectional"))
    )
    (net (code "17") (name "IAP-2") (class "Default")
      (node (ref "C17") (pin "1") (pinfunction "1_1") (pintype "passive"))
      (node (ref "IC2") (pin "3") (pinfunction "I1P_3") (pintype "input"))
      (node (ref "R14") (pin "8") (pinfunction "8_8") (pintype "bidirectional"))
    )
    (net (code "18") (name "IB+") (class "Default")
      (node (ref "CT2") (pin "2") (pinfunction "2_2") (pintype "passive"))
      (node (ref "CT2-2") (pin "2") (pinfunction "TIP_2") (pintype "passive"))
      (node (ref "R3") (pin "3") (pinfunction "3_3") (pintype "bidirectional"))
      (node (ref "R8") (pin "2") (pinfunction "2_2") (pintype "passive"))
    )
    (net (code "19") (name "IB+-2") (class "Default")
      (node (ref "CT5") (pin "2") (pinfunction "2_2") (pintype "passive"))
      (node (ref "CT5-2") (pin "2") (pinfunction "TIP_2") (pintype "passive"))
      (node (ref "R14") (pin "3") (pinfunction "3_3") (pintype "bidirectional"))
      (node (ref "R19") (pin "2") (pinfunction "2_2") (pintype "passive"))
    )
    (net (code "20") (name "IB-") (class "Default")
      (node (ref "CT2") (pin "1") (pinfunction "1_1") (pintype "passive"))
      (node (ref "CT2-2") (pin "1") (pinfunction "SLEEVE_1") (pintype "passive"))
      (node (ref "JP2") (pin "2") (pinfunction "2_2") (pintype "passive"))
      (node (ref "R3") (pin "4") (pinfunction "4_4") (pintype "bidirectional"))
    )
    (net (code "21") (name "IB--2") (class "Default")
      (node (ref "CT5") (pin "1") (pinfunction "1_1") (pintype "passive"))
      (node (ref "CT5-2") (pin "1") (pinfunction "SLEEVE_1") (pintype "passive"))
      (node (ref "JP5") (pin "2") (pinfunction "2_2") (pintype "passive"))
      (node (ref "R14") (pin "4") (pinfunction "4_4") (pintype "bidirectional"))
    )
    (net (code "22") (name "IBN") (class "Default")
      (node (ref "C5") (pin "2") (pinfunction "2_2") (pintype "passive"))
      (node (ref "IC1") (pin "6") (pinfunction "I2N_6") (pintype "input"))
      (node (ref "R3") (pin "5") (pinfunction "5_5") (pintype "bidirectional"))
    )
    (net (code "23") (name "IBN-2") (class "Default")
      (node (ref "C20") (pin "2") (pinfunction "2_2") (pintype "passive"))
      (node (ref "IC2") (pin "6") (pinfunction "I2N_6") (pintype "input"))
      (node (ref "R14") (pin "5") (pinfunction "5_5") (pintype "bidirectional"))
    )
    (net (code "24") (name "IBP") (class "Default")
      (node (ref "C4") (pin "1") (pinfunction "1_1") (pintype "passive"))
      (node (ref "IC1") (pin "5") (pinfunction "I2P_5") (pintype "input"))
      (node (ref "R3") (pin "6") (pinfunction "6_6") (pintype "bidirectional"))
    )
    (net (code "25") (name "IBP-2") (class "Default")
      (node (ref "C19") (pin "1") (pinfunction "1_1") (pintype "passive"))
      (node (ref "IC2") (pin "5") (pinfunction "I2P_5") (pintype "input"))
      (node (ref "R14") (pin "6") (pinfunction "6_6") (pintype "bidirectional"))
    )
    (net (code "26") (name "IC+") (class "Default")
      (node (ref "CT3") (pin "2") (pinfunction "2_2") (pintype "passive"))
      (node (ref "CT3-2") (pin "2") (pinfunction "TIP_2") (pintype "passive"))
      (node (ref "R4") (pin "2") (pinfunction "2_2") (pintype "passive"))
      (node (ref "R6") (pin "2") (pinfunction "2_2") (pintype "passive"))
    )
    (net (code "27") (name "IC+-2") (class "Default")
      (node (ref "CT6") (pin "2") (pinfunction "2_2") (pintype "passive"))
      (node (ref "CT6-2") (pin "2") (pinfunction "TIP_2") (pintype "passive"))
      (node (ref "R15") (pin "2") (pinfunction "2_2") (pintype "passive"))
      (node (ref "R17") (pin "2") (pinfunction "2_2") (pintype "passive"))
    )
    (net (code "28") (name "IC-") (class "Default")
      (node (ref "CT3") (pin "1") (pinfunction "1_1") (pintype "passive"))
      (node (ref "CT3-2") (pin "1") (pinfunction "SLEEVE_1") (pintype "passive"))
      (node (ref "JP3") (pin "2") (pinfunction "2_2") (pintype "passive"))
      (node (ref "R5") (pin "2") (pinfunction "2_2") (pintype "passive"))
    )
    (net (code "29") (name "IC--2") (class "Default")
      (node (ref "CT6") (pin "1") (pinfunction "1_1") (pintype "passive"))
      (node (ref "CT6-2") (pin "1") (pinfunction "SLEEVE_1") (pintype "passive"))
      (node (ref "JP6") (pin "2") (pinfunction "2_2") (pintype "passive"))
      (node (ref "R16") (pin "2") (pinfunction "2_2") (pintype "passive"))
    )
    (net (code "30") (name "ICN") (class "Default")
      (node (ref "C7") (pin "2") (pinfunction "2_2") (pintype "passive"))
      (node (ref "IC1") (pin "8") (pinfunction "I3N_8") (pintype "input"))
      (node (ref "R5") (pin "1") (pinfunction "1_1") (pintype "passive"))
    )
    (net (code "31") (name "ICN-2") (class "Default")
      (node (ref "C22") (pin "2") (pinfunction "2_2") (pintype "passive"))
      (node (ref "IC2") (pin "8") (pinfunction "I3N_8") (pintype "input"))
      (node (ref "R16") (pin "1") (pinfunction "1_1") (pintype "passive"))
    )
    (net (code "32") (name "ICP") (class "Default")
      (node (ref "C6") (pin "1") (pinfunction "1_1") (pintype "passive"))
      (node (ref "IC1") (pin "7") (pinfunction "I3P_7") (pintype "input"))
      (node (ref "R4") (pin "1") (pinfunction "1_1") (pintype "passive"))
    )
    (net (code "33") (name "ICP-2") (class "Default")
      (node (ref "C21") (pin "1") (pinfunction "1_1") (pintype "passive"))
      (node (ref "IC2") (pin "7") (pinfunction "I3P_7") (pintype "input"))
      (node (ref "R15") (pin "1") (pinfunction "1_1") (pintype "passive"))
    )
    (net (code "34") (name "IO0") (class "Default")
      (node (ref "J4") (pin "12") (pinfunction "12_12") (pintype "bidirectional"))
      (node (ref "U1") (pin "33") (pinfunction "IO0_33") (pintype "bidirectional"))
    )
    (net (code "35") (name "IO2") (class "Default")
      (node (ref "J4") (pin "11") (pinfunction "11_11") (pintype "bidirectional"))
      (node (ref "U1") (pin "34") (pinfunction "IO2_34") (pintype "bidirectional"))
    )
    (net (code "36") (name "IO12") (class "Default")
      (node (ref "J16") (pin "13") (pinfunction "13_13") (pintype "passive"))
      (node (ref "J4") (pin "10") (pinfunction "10_10") (pintype "bidirectional"))
      (node (ref "U1") (pin "13") (pinfunction "IO12_13") (pintype "bidirectional"))
    )
    (net (code "37") (name "IO13") (class "Default")
      (node (ref "J16") (pin "15") (pinfunction "15_15") (pintype "passive"))
      (node (ref "J4") (pin "9") (pinfunction "9_9") (pintype "bidirectional"))
      (node (ref "U1") (pin "15") (pinfunction "IO13_15") (pintype "bidirectional"))
    )
    (net (code "38") (name "IO14") (class "Default")
      (node (ref "J16") (pin "12") (pinfunction "12_12") (pintype "passive"))
      (node (ref "J4") (pin "8") (pinfunction "8_8") (pintype "bidirectional"))
      (node (ref "U1") (pin "12") (pinfunction "IO14_12") (pintype "bidirectional"))
    )
    (net (code "39") (name "IO15") (class "Default")
      (node (ref "J4") (pin "7") (pinfunction "7_7") (pintype "bidirectional"))
      (node (ref "U1") (pin "35") (pinfunction "IO15_35") (pintype "bidirectional"))
    )
    (net (code "40") (name "IO16") (class "Default")
      (node (ref "J7") (pin "12") (pinfunction "12_12") (pintype "bidirectional"))
      (node (ref "U1") (pin "31") (pinfunction "IO16_31") (pintype "bidirectional"))
    )
    (net (code "41") (name "IO17") (class "Default")
      (node (ref "J7") (pin "11") (pinfunction "11_11") (pintype "bidirectional"))
      (node (ref "U1") (pin "30") (pinfunction "IO17_30") (pintype "bidirectional"))
    )
    (net (code "42") (name "IO21") (class "Default")
      (node (ref "J7") (pin "10") (pinfunction "10_10") (pintype "bidirectional"))
      (node (ref "U1") (pin "25") (pinfunction "IO21_25") (pintype "bidirectional"))
    )
    (net (code "43") (name "IO22") (class "Default")
      (node (ref "J7") (pin "9") (pinfunction "9_9") (pintype "bidirectional"))
      (node (ref "U1") (pin "22") (pinfunction "IO22_22") (pintype "bidirectional"))
    )
    (net (code "44") (name "IO25") (class "Default")
      (node (ref "J16") (pin "9") (pinfunction "9_9") (pintype "passive"))
      (node (ref "J7") (pin "8") (pinfunction "8_8") (pintype "bidirectional"))
      (node (ref "U1") (pin "9") (pinfunction "IO25_9") (pintype "bidirectional"))
    )
    (net (code "45") (name "IO26") (class "Default")
      (node (ref "J16") (pin "10") (pinfunction "10_10") (pintype "passive"))
      (node (ref "J7") (pin "7") (pinfunction "7_7") (pintype "bidirectional"))
      (node (ref "U1") (pin "10") (pinfunction "IO26_10") (pintype "bidirectional"))
    )
    (net (code "46") (name "IO27") (class "Default")
      (node (ref "J16") (pin "11") (pinfunction "11_11") (pintype "passive"))
      (node (ref "U1") (pin "11") (pinfunction "IO27_11") (pintype "bidirectional"))
    )
    (net (code "47") (name "IO35") (class "Default")
      (node (ref "J16") (pin "6") (pinfunction "6_6") (pintype "passive"))
      (node (ref "U1") (pin "6") (pinfunction "IO35_6") (pintype "bidirectional"))
    )
    (net (code "48") (name "IRQ0") (class "Default")
      (node (ref "IC1") (pin "30") (pinfunction "IRQ0_30") (pintype "output"))
      (node (ref "IC2") (pin "30") (pinfunction "IRQ0_30") (pintype "output"))
      (node (ref "J16") (pin "7") (pinfunction "7_7") (pintype "passive"))
      (node (ref "U1") (pin "7") (pinfunction "IO32_7") (pintype "bidirectional"))
    )
    (net (code "49") (name "IRQ1") (class "Default")
      (node (ref "IC1") (pin "31") (pinfunction "IRQ1_31") (pintype "output"))
      (node (ref "IC2") (pin "31") (pinfunction "IRQ1_31") (pintype "output"))
      (node (ref "J16") (pin "8") (pinfunction "8_8") (pintype "passive"))
      (node (ref "U1") (pin "8") (pinfunction "IO33_8") (pintype "bidirectional"))
    )
    (net (code "50") (name "MISO") (class "Default")
      (node (ref "IC1") (pin "39") (pinfunction "SDO_39") (pintype "output"))
      (node (ref "IC2") (pin "39") (pinfunction "SDO_39") (pintype "output"))
      (node (ref "R13") (pin "2") (pinfunction "2_2") (pintype "bidirectional"))
      (node (ref "R2") (pin "2") (pinfunction "2_2") (pintype "bidirectional"))
      (node (ref "U1") (pin "27") (pinfunction "IO19_27") (pintype "bidirectional"))
    )
    (net (code "51") (name "MOSI") (class "Default")
      (node (ref "IC1") (pin "40") (pinfunction "SDI_40") (pintype "input"))
      (node (ref "IC2") (pin "40") (pinfunction "SDI_40") (pintype "input"))
      (node (ref "R13") (pin "1") (pinfunction "1_1") (pintype "bidirectional"))
      (node (ref "R2") (pin "1") (pinfunction "1_1") (pintype "bidirectional"))
      (node (ref "U1") (pin "21") (pinfunction "IO23_21") (pintype "bidirectional"))
    )
    (net (code "52") (name "Net-(C8-Pad2)") (class "Default")
      (node (ref "C8") (pin "2") (pinfunction "2_2") (pintype "passive"))
      (node (ref "C9") (pin "2") (pinfunction "2_2") (pintype "passive"))
      (node (ref "IC1") (pin "42") (pinfunction "VDD18_42") (pintype "power_in"))
      (node (ref "IC1") (pin "43") (pinfunction "VDD18_43") (pintype "power_in"))
    )
    (net (code "53") (name "Net-(C23-Pad2)") (class "Default")
      (node (ref "C23") (pin "2") (pinfunction "2_2") (pintype "passive"))
      (node (ref "C24") (pin "2") (pinfunction "2_2") (pintype "passive"))
      (node (ref "IC2") (pin "42") (pinfunction "VDD18_42") (pintype "power_in"))
      (node (ref "IC2") (pin "43") (pinfunction "VDD18_43") (pintype "power_in"))
    )
    (net (code "54") (name "Net-(CF1-2-PadA)") (class "Default")
      (node (ref "CF1-2") (pin "A") (pinfunction "A_A") (pintype "passive"))
      (node (ref "R20") (pin "1") (pinfunction "1_1") (pintype "passive"))
    )
    (net (code "55") (name "Net-(CF1-PadA)") (class "Default")
      (node (ref "CF1") (pin "A") (pinfunction "A_A") (pintype "passive"))
      (node (ref "R9") (pin "1") (pinfunction "1_1") (pintype "passive"))
    )
    (net (code "56") (name "Net-(IC1-OSCI)") (class "Default")
      (node (ref "IC1") (pin "20") (pinfunction "OSCI_20") (pintype "input"))
      (node (ref "Y1") (pin "1") (pinfunction "1_1") (pintype "passive"))
    )
    (net (code "57") (name "Net-(IC1-OSCO)") (class "Default")
      (node (ref "IC1") (pin "21") (pinfunction "OSCO_21") (pintype "output"))
      (node (ref "Y1") (pin "3") (pinfunction "2_3") (pintype "passive"))
    )
    (net (code "58") (name "Net-(IC1-VREF)") (class "Default")
      (node (ref "C12") (pin "1") (pinfunction "1_1") (pintype "passive"))
      (node (ref "C13") (pin "1") (pinfunction "1_1") (pintype "passive"))
      (node (ref "IC1") (pin "11") (pinfunction "VREF_11") (pintype "bidirectional"))
    )
    (net (code "59") (name "Net-(IC1-~{RESET})") (class "Default")
      (node (ref "C1") (pin "2") (pinfunction "2_2") (pintype "passive"))
      (node (ref "IC1") (pin "41") (pinfunction "~{RESET}_41") (pintype "input"))
      (node (ref "R1") (pin "2") (pinfunction "2_2") (pintype "passive"))
    )
    (net (code "60") (name "Net-(IC2-OSCI)") (class "Default")
      (node (ref "IC2") (pin "20") (pinfunction "OSCI_20") (pintype "input"))
      (node (ref "Y2") (pin "1") (pinfunction "1_1") (pintype "passive"))
    )
    (net (code "61") (name "Net-(IC2-OSCO)") (class "Default")
      (node (ref "IC2") (pin "21") (pinfunction "OSCO_21") (pintype "output"))
      (node (ref "Y2") (pin "3") (pinfunction "2_3") (pintype "passive"))
    )
    (net (code "62") (name "Net-(IC2-VREF)") (class "Default")
      (node (ref "C27") (pin "1") (pinfunction "1_1") (pintype "passive"))
      (node (ref "C28") (pin "1") (pinfunction "1_1") (pintype "passive"))
      (node (ref "IC2") (pin "11") (pinfunction "VREF_11") (pintype "bidirectional"))
    )
    (net (code "63") (name "Net-(IC2-~{RESET})") (class "Default")
      (node (ref "C16") (pin "2") (pinfunction "2_2") (pintype "passive"))
      (node (ref "IC2") (pin "41") (pinfunction "~{RESET}_41") (pintype "input"))
      (node (ref "R12") (pin "2") (pinfunction "2_2") (pintype "passive"))
    )
    (net (code "64") (name "Net-(JP1-Pad1)") (class "Default")
      (node (ref "JP1") (pin "1") (pinfunction "1_1") (pintype "passive"))
      (node (ref "R7") (pin "1") (pinfunction "1_1") (pintype "passive"))
    )
    (net (code "65") (name "Net-(JP2-Pad1)") (class "Default")
      (node (ref "JP2") (pin "1") (pinfunction "1_1") (pintype "passive"))
      (node (ref "R8") (pin "1") (pinfunction "1_1") (pintype "passive"))
    )
    (net (code "66") (name "Net-(JP3-Pad1)") (class "Default")
      (node (ref "JP3") (pin "1") (pinfunction "1_1") (pintype "passive"))
      (node (ref "R6") (pin "1") (pinfunction "1_1") (pintype "passive"))
    )
    (net (code "67") (name "Net-(JP4-Pad1)") (class "Default")
      (node (ref "JP4") (pin "1") (pinfunction "1_1") (pintype "passive"))
      (node (ref "R18") (pin "1") (pinfunction "1_1") (pintype "passive"))
    )
    (net (code "68") (name "Net-(JP5-Pad1)") (class "Default")
      (node (ref "JP5") (pin "1") (pinfunction "1_1") (pintype "passive"))
      (node (ref "R19") (pin "1") (pinfunction "1_1") (pintype "passive"))
    )
    (net (code "69") (name "Net-(JP6-Pad1)") (class "Default")
      (node (ref "JP6") (pin "1") (pinfunction "1_1") (pintype "passive"))
      (node (ref "R17") (pin "1") (pinfunction "1_1") (pintype "passive"))
    )
    (net (code "70") (name "Net-(PWR-PadA)") (class "Default")
      (node (ref "PWR") (pin "A") (pinfunction "A_A") (pintype "passive"))
      (node (ref "R10") (pin "1") (pinfunction "1_1") (pintype "passive"))
    )
    (net (code "71") (name "Net-(U1-CMD)") (class "Default")
      (node (ref "J16") (pin "18") (pinfunction "18_18") (pintype "passive"))
      (node (ref "U1") (pin "18") (pinfunction "CMD_18") (pintype "bidirectional"))
    )
    (net (code "72") (name "Net-(U1-EN)") (class "Default")
      (node (ref "J16") (pin "2") (pinfunction "2_2") (pintype "passive"))
      (node (ref "U1") (pin "2") (pinfunction "EN_2") (pintype "input"))
    )
    (net (code "73") (name "Net-(U1-EXT_5V)") (class "Default")
      (node (ref "J16") (pin "19") (pinfunction "19_19") (pintype "passive"))
      (node (ref "U1") (pin "19") (pinfunction "EXT_5V_19") (pintype "power_in"))
    )
    (net (code "74") (name "Net-(U1-SD2)") (class "Default")
      (node (ref "J16") (pin "16") (pinfunction "16_16") (pintype "passive"))
      (node (ref "U1") (pin "16") (pinfunction "SD2_16") (pintype "bidirectional"))
    )
    (net (code "75") (name "Net-(U1-SD3)") (class "Default")
      (node (ref "J16") (pin "17") (pinfunction "17_17") (pintype "passive"))
      (node (ref "U1") (pin "17") (pinfunction "SD3_17") (pintype "bidirectional"))
    )
    (net (code "76") (name "Net-(U1-SENSOR_VN)") (class "Default")
      (node (ref "J16") (pin "4") (pinfunction "4_4") (pintype "passive"))
      (node (ref "U1") (pin "4") (pinfunction "SENSOR_VN_4") (pintype "input"))
    )
    (net (code "77") (name "Net-(U1-SENSOR_VP)") (class "Default")
      (node (ref "J16") (pin "3") (pinfunction "3_3") (pintype "passive"))
      (node (ref "U1") (pin "3") (pinfunction "SENSOR_VP_3") (pintype "input"))
    )
    (net (code "78") (name "SCLK") (class "Default")
      (node (ref "IC1") (pin "38") (pinfunction "SCLK_38") (pintype "input"))
      (node (ref "IC2") (pin "38") (pinfunction "SCLK_38") (pintype "input"))
      (node (ref "R13") (pin "3") (pinfunction "3_3") (pintype "bidirectional"))
      (node (ref "R2") (pin "3") (pinfunction "3_3") (pintype "bidirectional"))
      (node (ref "U1") (pin "28") (pinfunction "IO18_28") (pintype "bidirectional"))
    )
    (net (code "79") (name "V2N") (class "Default")
      (node (ref "IC1") (pin "16") (pinfunction "V2N_16") (pintype "input"))
      (node (ref "JP9") (pin "3") (pinfunction "3_3") (pintype "passive"))
    )
    (net (code "80") (name "V2N-2") (class "Default")
      (node (ref "IC2") (pin "16") (pinfunction "V2N_16") (pintype "input"))
      (node (ref "JP11") (pin "3") (pinfunction "3_3") (pintype "passive"))
    )
    (net (code "81") (name "V2P") (class "Default")
      (node (ref "IC1") (pin "15") (pinfunction "V2P_15") (pintype "input"))
      (node (ref "JP8") (pin "3") (pinfunction "3_3") (pintype "passive"))
    )
    (net (code "82") (name "V2P-2") (class "Default")
      (node (ref "IC2") (pin "15") (pinfunction "V2P_15") (pintype "input"))
      (node (ref "JP10") (pin "3") (pinfunction "3_3") (pintype "passive"))
    )
    (net (code "83") (name "V3N") (class "Default")
      (node (ref "IC1") (pin "18") (pinfunction "V3N_18") (pintype "input"))
      (node (ref "JP9") (pin "1") (pinfunction "1_1") (pintype "passive"))
    )
    (net (code "84") (name "V3N-2") (class "Default")
      (node (ref "IC2") (pin "18") (pinfunction "V3N_18") (pintype "input"))
      (node (ref "JP11") (pin "1") (pinfunction "1_1") (pintype "passive"))
    )
    (net (code "85") (name "V3P") (class "Default")
      (node (ref "IC1") (pin "17") (pinfunction "V3P_17") (pintype "input"))
      (node (ref "JP8") (pin "1") (pinfunction "1_1") (pintype "passive"))
    )
    (net (code "86") (name "V3P-2") (class "Default")
      (node (ref "IC2") (pin "17") (pinfunction "V3P_17") (pintype "input"))
      (node (ref "JP10") (pin "1") (pinfunction "1_1") (pintype "passive"))
    )
    (net (code "87") (name "VA+") (class "Default")
      (node (ref "J8") (pin "1") (pinfunction "1_1") (pintype "passive"))
      (node (ref "JP12") (pin "2") (pinfunction "2_2") (pintype "passive"))
      (node (ref "R26") (pin "2") (pinfunction "2_2") (pintype "passive"))
    )
    (net (code "88") (name "VA-") (class "Default")
      (node (ref "J6") (pin "1") (pinfunction "1_1") (pintype "passive"))
      (node (ref "JP13") (pin "2") (pinfunction "2_2") (pintype "passive"))
      (node (ref "R34") (pin "2") (pinfunction "2_2") (pintype "passive"))
    )
    (net (code "89") (name "VA2+") (class "Default")
      (node (ref "J3") (pin "1") (pinfunction "1_1") (pintype "passive"))
      (node (ref "JP12") (pin "1") (pinfunction "1_1") (pintype "passive"))
      (node (ref "R28") (pin "2") (pinfunction "2_2") (pintype "passive"))
    )
    (net (code "90") (name "VA2-") (class "Default")
      (node (ref "J3") (pin "2") (pinfunction "2_2") (pintype "passive"))
      (node (ref "JP13") (pin "1") (pinfunction "1_1") (pintype "passive"))
      (node (ref "R32") (pin "2") (pinfunction "2_2") (pintype "passive"))
    )
    (net (code "91") (name "VAN") (class "Default")
      (node (ref "C15") (pin "1") (pinfunction "1_1") (pintype "passive"))
      (node (ref "IC1") (pin "14") (pinfunction "V1N_14") (pintype "input"))
      (node (ref "JP9") (pin "2") (pinfunction "2_2") (pintype "passive"))
      (node (ref "R11") (pin "6") (pinfunction "6_6") (pintype "bidirectional"))
      (node (ref "R24") (pin "7") (pinfunction "7_7") (pintype "bidirectional"))
      (node (ref "R34") (pin "1") (pinfunction "1_1") (pintype "passive"))
    )
    (net (code "92") (name "VAN2") (class "Default")
      (node (ref "C30") (pin "1") (pinfunction "1_1") (pintype "passive"))
      (node (ref "IC2") (pin "14") (pinfunction "V1N_14") (pintype "input"))
      (node (ref "JP11") (pin "2") (pinfunction "2_2") (pintype "passive"))
      (node (ref "R11") (pin "5") (pinfunction "5_5") (pintype "bidirectional"))
      (node (ref "R24") (pin "8") (pinfunction "8_8") (pintype "bidirectional"))
      (node (ref "R32") (pin "1") (pinfunction "1_1") (pintype "passive"))
    )
    (net (code "93") (name "VAP") (class "Default")
      (node (ref "C14") (pin "1") (pinfunction "1_1") (pintype "passive"))
      (node (ref "IC1") (pin "13") (pinfunction "V1P_13") (pintype "input"))
      (node (ref "JP8") (pin "2") (pinfunction "2_2") (pintype "passive"))
      (node (ref "R11") (pin "7") (pinfunction "7_7") (pintype "bidirectional"))
      (node (ref "R24") (pin "6") (pinfunction "6_6") (pintype "bidirectional"))
      (node (ref "R26") (pin "1") (pinfunction "1_1") (pintype "passive"))
    )
    (net (code "94") (name "VAP2") (class "Default")
      (node (ref "C29") (pin "1") (pinfunction "1_1") (pintype "passive"))
      (node (ref "IC2") (pin "13") (pinfunction "V1P_13") (pintype "input"))
      (node (ref "JP10") (pin "2") (pinfunction "2_2") (pintype "passive"))
      (node (ref "R11") (pin "8") (pinfunction "8_8") (pintype "bidirectional"))
      (node (ref "R24") (pin "5") (pinfunction "5_5") (pintype "bidirectional"))
      (node (ref "R28") (pin "1") (pinfunction "1_1") (pintype "passive"))
    )
    (net (code "95") (name "VDD") (class "Default")
      (node (ref "C10") (pin "2") (pinfunction "2_2") (pintype "passive"))
      (node (ref "C11") (pin "2") (pinfunction "2_2") (pintype "passive"))
      (node (ref "C25") (pin "2") (pinfunction "2_2") (pintype "passive"))
      (node (ref "C26") (pin "2") (pinfunction "2_2") (pintype "passive"))
      (node (ref "IC1") (pin "1") (pinfunction "AVDD_1") (pintype "power_in"))
      (node (ref "IC1") (pin "33") (pinfunction "PM0_33") (pintype "input"))
      (node (ref "IC1") (pin "34") (pinfunction "PM1_34") (pintype "input"))
      (node (ref "IC1") (pin "48") (pinfunction "DVDD_48") (pintype "power_in"))
      (node (ref "IC2") (pin "1") (pinfunction "AVDD_1") (pintype "power_in"))
      (node (ref "IC2") (pin "33") (pinfunction "PM0_33") (pintype "input"))
      (node (ref "IC2") (pin "34") (pinfunction "PM1_34") (pintype "input"))
      (node (ref "IC2") (pin "48") (pinfunction "DVDD_48") (pintype "power_in"))
      (node (ref "J16") (pin "1") (pinfunction "1_1") (pintype "passive"))
      (node (ref "R1") (pin "1") (pinfunction "1_1") (pintype "passive"))
      (node (ref "R10") (pin "2") (pinfunction "2_2") (pintype "passive"))
      (node (ref "R12") (pin "1") (pinfunction "1_1") (pintype "passive"))
      (node (ref "R13") (pin "5") (pinfunction "5_5") (pintype "bidirectional"))
      (node (ref "R13") (pin "6") (pinfunction "6_6") (pintype "bidirectional"))
      (node (ref "R13") (pin "7") (pinfunction "7_7") (pintype "bidirectional"))
      (node (ref "R13") (pin "8") (pinfunction "8_8") (pintype "bidirectional"))
      (node (ref "R2") (pin "5") (pinfunction "5_5") (pintype "bidirectional"))
      (node (ref "R2") (pin "6") (pinfunction "6_6") (pintype "bidirectional"))
      (node (ref "R2") (pin "7") (pinfunction "7_7") (pintype "bidirectional"))
      (node (ref "R2") (pin "8") (pinfunction "8_8") (pintype "bidirectional"))
      (node (ref "R24") (pin "1") (pinfunction "1_1") (pintype "bidirectional"))
      (node (ref "R24") (pin "2") (pinfunction "2_2") (pintype "bidirectional"))
      (node (ref "R24") (pin "3") (pinfunction "3_3") (pintype "bidirectional"))
      (node (ref "R24") (pin "4") (pinfunction "4_4") (pintype "bidirectional"))
      (node (ref "U1") (pin "1") (pinfunction "3V3_1") (pintype "power_in"))
    )
    (net (code "96") (name "WARN") (class "Default")
      (node (ref "IC1") (pin "29") (pinfunction "WARNOUT_29") (pintype "output"))
      (node (ref "IC2") (pin "29") (pinfunction "WARNOUT_29") (pintype "output"))
      (node (ref "J16") (pin "5") (pinfunction "5_5") (pintype "passive"))
      (node (ref "U1") (pin "5") (pinfunction "IO34_5") (pintype "bidirectional"))
    )
    (net (code "97") (name "ZX0") (class "Default")
      (node (ref "IC1") (pin "22") (pinfunction "ZX0_22") (pintype "output"))
      (node (ref "ZX0") (pin "1") (pinfunction "P_1") (pintype "passive"))
    )
    (net (code "98") (name "ZX0-2") (class "Default")
      (node (ref "IC2") (pin "22") (pinfunction "ZX0_22") (pintype "output"))
      (node (ref "ZX0-2") (pin "1") (pinfunction "P_1") (pintype "passive"))
    )
    (net (code "99") (name "ZX1") (class "Default")
      (node (ref "IC1") (pin "23") (pinfunction "ZX1_23") (pintype "output"))
      (node (ref "ZX1") (pin "1") (pinfunction "P_1") (pintype "passive"))
    )
    (net (code "100") (name "ZX1-2") (class "Default")
      (node (ref "IC2") (pin "23") (pinfunction "ZX1_23") (pintype "output"))
      (node (ref "ZX1-2") (pin "1") (pinfunction "P_1") (pintype "passive"))
    )
    (net (code "101") (name "ZX2") (class "Default")
      (node (ref "IC1") (pin "24") (pinfunction "ZX2_24") (pintype "output"))
      (node (ref "ZX2") (pin "1") (pinfunction "P_1") (pintype "passive"))
    )
    (net (code "102") (name "ZX2-2") (class "Default")
      (node (ref "IC2") (pin "24") (pinfunction "ZX2_24") (pintype "output"))
      (node (ref "ZX2-2") (pin "1") (pinfunction "P_1") (pintype "passive"))
    )
    (net (code "103") (name "unconnected-(CT1-2-RING-Pad3)") (class "Default")
      (node (ref "CT1-2") (pin "3") (pinfunction "RING_3") (pintype "passive"))
    )
    (net (code "104") (name "unconnected-(CT1-2-TIP_SWITCH-Pad10)") (class "Default")
      (node (ref "CT1-2") (pin "10") (pinfunction "TIP_SWITCH_10") (pintype "passive"))
    )
    (net (code "105") (name "unconnected-(CT2-2-RING-Pad3)") (class "Default")
      (node (ref "CT2-2") (pin "3") (pinfunction "RING_3") (pintype "passive"))
    )
    (net (code "106") (name "unconnected-(CT2-2-TIP_SWITCH-Pad10)") (class "Default")
      (node (ref "CT2-2") (pin "10") (pinfunction "TIP_SWITCH_10") (pintype "passive"))
    )
    (net (code "107") (name "unconnected-(CT3-2-RING-Pad3)") (class "Default")
      (node (ref "CT3-2") (pin "3") (pinfunction "RING_3") (pintype "passive"))
    )
    (net (code "108") (name "unconnected-(CT3-2-TIP_SWITCH-Pad10)") (class "Default")
      (node (ref "CT3-2") (pin "10") (pinfunction "TIP_SWITCH_10") (pintype "passive"))
    )
    (net (code "109") (name "unconnected-(CT4-2-RING-Pad3)") (class "Default")
      (node (ref "CT4-2") (pin "3") (pinfunction "RING_3") (pintype "passive"))
    )
    (net (code "110") (name "unconnected-(CT4-2-TIP_SWITCH-Pad10)") (class "Default")
      (node (ref "CT4-2") (pin "10") (pinfunction "TIP_SWITCH_10") (pintype "passive"))
    )
    (net (code "111") (name "unconnected-(CT5-2-RING-Pad3)") (class "Default")
      (node (ref "CT5-2") (pin "3") (pinfunction "RING_3") (pintype "passive"))
    )
    (net (code "112") (name "unconnected-(CT5-2-TIP_SWITCH-Pad10)") (class "Default")
      (node (ref "CT5-2") (pin "10") (pinfunction "TIP_SWITCH_10") (pintype "passive"))
    )
    (net (code "113") (name "unconnected-(CT6-2-RING-Pad3)") (class "Default")
      (node (ref "CT6-2") (pin "3") (pinfunction "RING_3") (pintype "passive"))
    )
    (net (code "114") (name "unconnected-(CT6-2-TIP_SWITCH-Pad10)") (class "Default")
      (node (ref "CT6-2") (pin "10") (pinfunction "TIP_SWITCH_10") (pintype "passive"))
    )
    (net (code "115") (name "unconnected-(IC1-I4N-Pad10)") (class "Default")
      (node (ref "IC1") (pin "10") (pinfunction "I4N_10") (pintype "input"))
    )
    (net (code "116") (name "unconnected-(IC1-I4P-Pad9)") (class "Default")
      (node (ref "IC1") (pin "9") (pinfunction "I4P_9") (pintype "input"))
    )
    (net (code "117") (name "unconnected-(IC1-NC-Pad35)") (class "Default")
      (node (ref "IC1") (pin "35") (pinfunction "NC_35") (pintype "no_connect"))
    )
    (net (code "118") (name "unconnected-(IC1-NC-Pad45)") (class "Default")
      (node (ref "IC1") (pin "45") (pinfunction "NC_45") (pintype "no_connect"))
    )
    (net (code "119") (name "unconnected-(IC1-NC-Pad46)") (class "Default")
      (node (ref "IC1") (pin "46") (pinfunction "NC_46") (pintype "no_connect"))
    )
    (net (code "120") (name "unconnected-(IC2-I4N-Pad10)") (class "Default")
      (node (ref "IC2") (pin "10") (pinfunction "I4N_10") (pintype "input"))
    )
    (net (code "121") (name "unconnected-(IC2-I4P-Pad9)") (class "Default")
      (node (ref "IC2") (pin "9") (pinfunction "I4P_9") (pintype "input"))
    )
    (net (code "122") (name "unconnected-(IC2-NC-Pad35)") (class "Default")
      (node (ref "IC2") (pin "35") (pinfunction "NC_35") (pintype "no_connect"))
    )
    (net (code "123") (name "unconnected-(IC2-NC-Pad45)") (class "Default")
      (node (ref "IC2") (pin "45") (pinfunction "NC_45") (pintype "no_connect"))
    )
    (net (code "124") (name "unconnected-(IC2-NC-Pad46)") (class "Default")
      (node (ref "IC2") (pin "46") (pinfunction "NC_46") (pintype "no_connect"))
    )
    (net (code "125") (name "unconnected-(J5-Pad1)") (class "Default")
      (node (ref "J5") (pin "1") (pinfunction "1_1") (pintype "passive"))
    )
    (net (code "126") (name "unconnected-(U1-CLK-Pad38)") (class "Default")
      (node (ref "U1") (pin "38") (pinfunction "CLK_38") (pintype "input"))
    )
    (net (code "127") (name "unconnected-(U1-IO4-Pad32)") (class "Default")
      (node (ref "U1") (pin "32") (pinfunction "IO4_32") (pintype "bidirectional"))
    )
    (net (code "128") (name "unconnected-(U1-IO5-Pad29)") (class "Default")
      (node (ref "U1") (pin "29") (pinfunction "IO5_29") (pintype "bidirectional"))
    )
    (net (code "129") (name "unconnected-(U1-RXD0-Pad24)") (class "Default")
      (node (ref "U1") (pin "24") (pinfunction "RXD0_24") (pintype "input"))
    )
    (net (code "130") (name "unconnected-(U1-SD0-Pad37)") (class "Default")
      (node (ref "U1") (pin "37") (pinfunction "SD0_37") (pintype "bidirectional"))
    )
    (net (code "131") (name "unconnected-(U1-SD1-Pad36)") (class "Default")
      (node (ref "U1") (pin "36") (pinfunction "SD1_36") (pintype "bidirectional"))
    )
    (net (code "132") (name "unconnected-(U1-TXD0-Pad23)") (class "Default")
      (node (ref "U1") (pin "23") (pinfunction "TXD0_23") (pintype "output"))
    )
    (net (code "133") (name "~{CS-2}") (class "Default")
      (node (ref "IC2") (pin "37") (pinfunction "~{CS}_37") (pintype "input"))
      (node (ref "J7") (pin "1") (pinfunction "1_1") (pintype "bidirectional"))
      (node (ref "J7") (pin "2") (pinfunction "2_2") (pintype "bidirectional"))
      (node (ref "J7") (pin "3") (pinfunction "3_3") (pintype "bidirectional"))
      (node (ref "J7") (pin "4") (pinfunction "4_4") (pintype "bidirectional"))
      (node (ref "J7") (pin "5") (pinfunction "5_5") (pintype "bidirectional"))
      (node (ref "J7") (pin "6") (pinfunction "6_6") (pintype "bidirectional"))
      (node (ref "R13") (pin "4") (pinfunction "4_4") (pintype "bidirectional"))
    )
    (net (code "134") (name "~{CS}") (class "Default")
      (node (ref "IC1") (pin "37") (pinfunction "~{CS}_37") (pintype "input"))
      (node (ref "J4") (pin "1") (pinfunction "1_1") (pintype "bidirectional"))
      (node (ref "J4") (pin "2") (pinfunction "2_2") (pintype "bidirectional"))
      (node (ref "J4") (pin "3") (pinfunction "3_3") (pintype "bidirectional"))
      (node (ref "J4") (pin "4") (pinfunction "4_4") (pintype "bidirectional"))
      (node (ref "J4") (pin "5") (pinfunction "5_5") (pintype "bidirectional"))
      (node (ref "J4") (pin "6") (pinfunction "6_6") (pintype "bidirectional"))
      (node (ref "R2") (pin "4") (pinfunction "4_4") (pintype "bidirectional"))
    )
  )
)
